# Sheet.net
KiCad netlist of a schematic drawn in Altium Designer
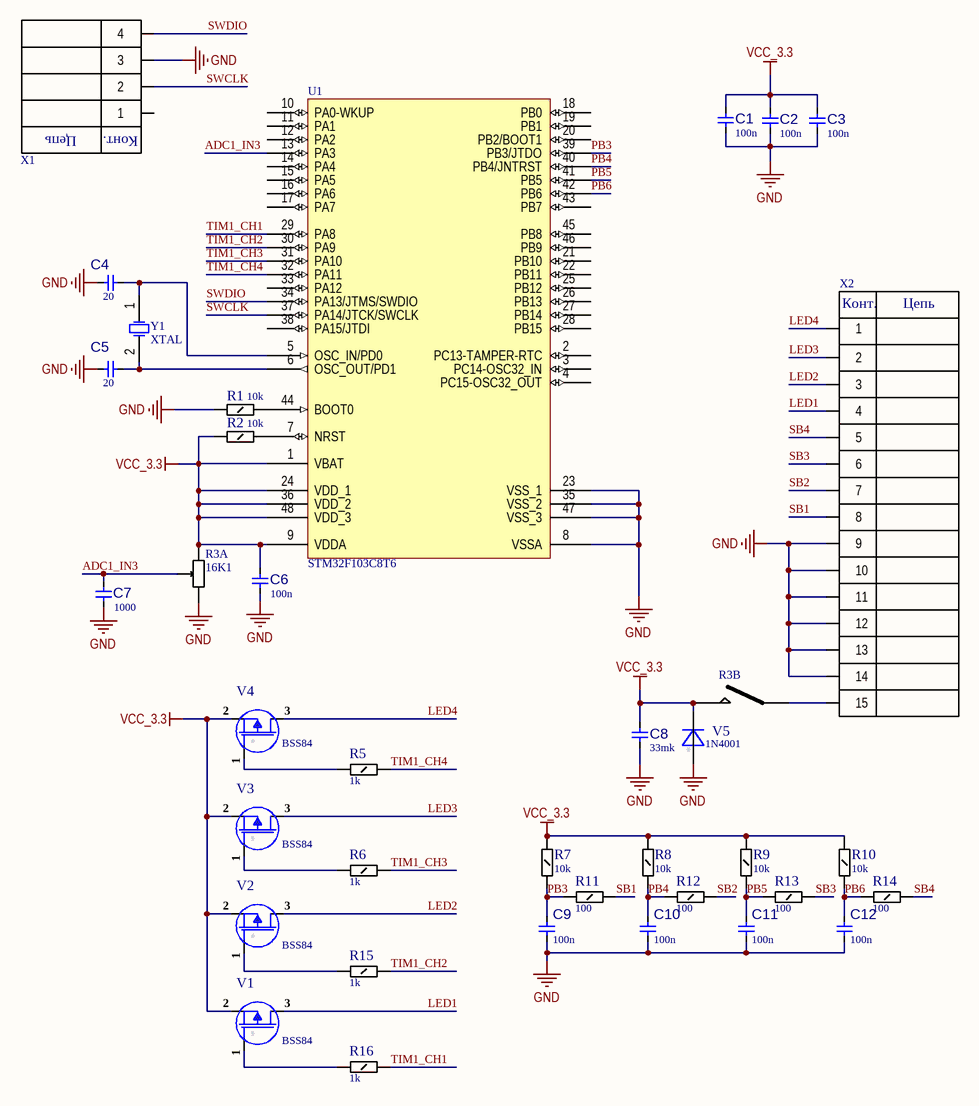
[diagram p0: Sheet.SchDoc]

(export (version "E")
  (design (tool "Eeschema 10.0.6"))
  (components
    (comp (ref "C1")
      (value "100n")
      (footprint "C1206")
      (fields (field (name "PART NUMBER") "Condensator 1206 100") (field (name "Comment") "C1206"))
      (libsource (lib "Database_Libs") (part "C1206"))
    )
    (comp (ref "C2")
      (value "100n")
      (footprint "C1206")
      (fields (field (name "PART NUMBER") "Condensator 1206 100") (field (name "Comment") "C1206"))
      (libsource (lib "Database_Libs") (part "C1206"))
    )
    (comp (ref "C3")
      (value "100n")
      (footprint "C1206")
      (fields (field (name "PART NUMBER") "Condensator 1206 100") (field (name "Comment") "C1206"))
      (libsource (lib "Database_Libs") (part "C1206"))
    )
    (comp (ref "C4")
      (value "20")
      (footprint "C1206")
      (fields (field (name "PART NUMBER") "Condensator 1206 20") (field (name "Comment") "C1206"))
      (libsource (lib "Database_Libs") (part "C1206"))
    )
    (comp (ref "C5")
      (value "20")
      (footprint "C1206")
      (fields (field (name "PART NUMBER") "Condensator 1206 20") (field (name "Comment") "C1206"))
      (libsource (lib "Database_Libs") (part "C1206"))
    )
    (comp (ref "C6")
      (value "100n")
      (footprint "C1206")
      (fields (field (name "PART NUMBER") "Condensator 1206 100") (field (name "Comment") "C1206"))
      (libsource (lib "Database_Libs") (part "C1206"))
    )
    (comp (ref "C7")
      (value "1000")
      (footprint "C1206")
      (fields (field (name "PART NUMBER") "Condensator 1206 100") (field (name "Comment") "C1206"))
      (libsource (lib "Database_Libs") (part "C1206"))
    )
    (comp (ref "C8")
      (value "33mk")
      (footprint "C1210")
      (fields (field (name "PART NUMBER") "Condensator 1210 33mk"))
      (libsource (lib "Database_Libs") (part "C1210"))
    )
    (comp (ref "C9")
      (value "100n")
      (footprint "C1206")
      (fields (field (name "PART NUMBER") "Condensator 1206 100") (field (name "Comment") "C1206"))
      (libsource (lib "Database_Libs") (part "C1206"))
    )
    (comp (ref "C10")
      (value "100n")
      (footprint "C1206")
      (fields (field (name "PART NUMBER") "Condensator 1206 100") (field (name "Comment") "C1206"))
      (libsource (lib "Database_Libs") (part "C1206"))
    )
    (comp (ref "C11")
      (value "100n")
      (footprint "C1206")
      (fields (field (name "PART NUMBER") "Condensator 1206 100") (field (name "Comment") "C1206"))
      (libsource (lib "Database_Libs") (part "C1206"))
    )
    (comp (ref "C12")
      (value "100n")
      (footprint "C1206")
      (fields (field (name "PART NUMBER") "Condensator 1206 100") (field (name "Comment") "C1206"))
      (libsource (lib "Database_Libs") (part "C1206"))
    )
    (comp (ref "R1")
      (value "10k")
      (footprint "R1206")
      (fields (field (name "PART NUMBER") "Resistor 1206 10k") (field (name "Comment") "R1206-0,25 W"))
      (libsource (lib "Database_Libs") (part "R1206-0,25 W"))
    )
    (comp (ref "R2")
      (value "10k")
      (footprint "R1206")
      (fields (field (name "PART NUMBER") "Resistor 1206 10k") (field (name "Comment") "R1206-0,25 W"))
      (libsource (lib "Database_Libs") (part "R1206-0,25 W"))
    )
    (comp (ref "R3")
      (value "16K1")
      (footprint "S16KN1")
      (fields (field (name "PART NUMBER") "Resistor S16KN1"))
      (libsource (lib "Database_Libs") (part "16K1"))
    )
    (comp (ref "R5")
      (value "1k")
      (footprint "R1206")
      (fields (field (name "PART NUMBER") "Resistor 1206 10k") (field (name "Comment") "R1206-0,25 W"))
      (libsource (lib "Database_Libs") (part "R1206-0,25 W"))
    )
    (comp (ref "R6")
      (value "1k")
      (footprint "R1206")
      (fields (field (name "PART NUMBER") "Resistor 1206 10k") (field (name "Comment") "R1206-0,25 W"))
      (libsource (lib "Database_Libs") (part "R1206-0,25 W"))
    )
    (comp (ref "R7")
      (value "10k")
      (footprint "R1206")
      (fields (field (name "PART NUMBER") "Resistor 1206 10k") (field (name "Comment") "R1206-0,25 W"))
      (libsource (lib "Database_Libs") (part "R1206-0,25 W"))
    )
    (comp (ref "R8")
      (value "10k")
      (footprint "R1206")
      (fields (field (name "PART NUMBER") "Resistor 1206 10k") (field (name "Comment") "R1206-0,25 W"))
      (libsource (lib "Database_Libs") (part "R1206-0,25 W"))
    )
    (comp (ref "R9")
      (value "10k")
      (footprint "R1206")
      (fields (field (name "PART NUMBER") "Resistor 1206 10k") (field (name "Comment") "R1206-0,25 W"))
      (libsource (lib "Database_Libs") (part "R1206-0,25 W"))
    )
    (comp (ref "R10")
      (value "10k")
      (footprint "R1206")
      (fields (field (name "PART NUMBER") "Resistor 1206 10k") (field (name "Comment") "R1206-0,25 W"))
      (libsource (lib "Database_Libs") (part "R1206-0,25 W"))
    )
    (comp (ref "R11")
      (value "100")
      (footprint "R1206")
      (fields (field (name "PART NUMBER") "Resistor 1206 10k") (field (name "Comment") "R1206-0,25 W"))
      (libsource (lib "Database_Libs") (part "R1206-0,25 W"))
    )
    (comp (ref "R12")
      (value "100")
      (footprint "R1206")
      (fields (field (name "PART NUMBER") "Resistor 1206 10k") (field (name "Comment") "R1206-0,25 W"))
      (libsource (lib "Database_Libs") (part "R1206-0,25 W"))
    )
    (comp (ref "R13")
      (value "100")
      (footprint "R1206")
      (fields (field (name "PART NUMBER") "Resistor 1206 10k") (field (name "Comment") "R1206-0,25 W"))
      (libsource (lib "Database_Libs") (part "R1206-0,25 W"))
    )
    (comp (ref "R14")
      (value "100")
      (footprint "R1206")
      (fields (field (name "PART NUMBER") "Resistor 1206 10k") (field (name "Comment") "R1206-0,25 W"))
      (libsource (lib "Database_Libs") (part "R1206-0,25 W"))
    )
    (comp (ref "R15")
      (value "1k")
      (footprint "R1206")
      (fields (field (name "PART NUMBER") "Resistor 1206 10k") (field (name "Comment") "R1206-0,25 W"))
      (libsource (lib "Database_Libs") (part "R1206-0,25 W"))
    )
    (comp (ref "R16")
      (value "1k")
      (footprint "R1206")
      (fields (field (name "PART NUMBER") "Resistor 1206 10k") (field (name "Comment") "R1206-0,25 W"))
      (libsource (lib "Database_Libs") (part "R1206-0,25 W"))
    )
    (comp (ref "U1")
      (value "STM32F103C8T6")
      (footprint "LQFP48_N")
      (description "STM32 ARM-based 32-bit MCU with 64 Kbytes Flash, 48-pin LQFP, Industrial Temperature")
      (fields (field (name "PUBLISHER") "Altium Limited"))
      (libsource (lib "ST Microcontroller 32-Bit STM32") (part "STM32F103C8T6"))
    )
    (comp (ref "V1") (value "BSS84") (footprint "SOT-23") (libsource (lib "Database_Libs") (part "BSS84")))
    (comp (ref "V2") (value "BSS84") (footprint "SOT-23") (libsource (lib "Database_Libs") (part "BSS84")))
    (comp (ref "V3") (value "BSS84") (footprint "SOT-23") (libsource (lib "Database_Libs") (part "BSS84")))
    (comp (ref "V4") (value "BSS84") (footprint "SOT-23") (libsource (lib "Database_Libs") (part "BSS84")))
    (comp (ref "V5")
      (value "1N4001")
      (footprint "doid")
      (fields (field (name "PART NUMBER") "1N4007"))
      (libsource (lib "Database_Libs") (part "1N4001"))
    )
    (comp (ref "X1")
      (value "PLS-4R")
      (footprint "PLS-4R")
      (fields (field (name "PART NUMBER") "Разъем PLS-4R"))
      (libsource (lib "Database_Libs") (part "PLS-4R"))
    )
    (comp (ref "X2")
      (value "sourse")
      (footprint "DHR15-FB")
      (fields (field (name "PART NUMBER") "DHR-15FB"))
      (libsource (lib "Database_Libs") (part "DHR"))
    )
    (comp (ref "Y1")
      (value "XTAL")
      (footprint "Crystal Oscillator:HC49/4H_SMX")
      (description "Crystal Oscillator")
      (fields (field (name "PUBLISHER") "Altium Limited"))
      (libsource (lib "Miscellaneous Devices") (part "XTAL"))
    )
  )
  (nets
    (net (code "1") (name "/ADC1_IN3") (class "Default")
      (node (ref "C7") (pin "2") (pinfunction "2_2") (pintype "passive"))
      (node (ref "R3") (pin "2") (pinfunction "2_2") (pintype "passive"))
      (node (ref "U1") (pin "13") (pinfunction "PA3_13") (pintype "bidirectional"))
    )
    (net (code "2") (name "/LED1") (class "Default")
      (node (ref "V1") (pin "3") (pinfunction "D_3") (pintype "passive"))
      (node (ref "X2") (pin "4") (pinfunction "4_4") (pintype "passive"))
    )
    (net (code "3") (name "/LED2") (class "Default")
      (node (ref "V2") (pin "3") (pinfunction "D_3") (pintype "passive"))
      (node (ref "X2") (pin "3") (pinfunction "3_3") (pintype "passive"))
    )
    (net (code "4") (name "/LED3") (class "Default")
      (node (ref "V3") (pin "3") (pinfunction "D_3") (pintype "passive"))
      (node (ref "X2") (pin "2") (pinfunction "2_2") (pintype "passive"))
    )
    (net (code "5") (name "/LED4") (class "Default")
      (node (ref "V4") (pin "3") (pinfunction "D_3") (pintype "passive"))
      (node (ref "X2") (pin "1") (pinfunction "1_1") (pintype "passive"))
    )
    (net (code "6") (name "/PB3") (class "Default")
      (node (ref "C9") (pin "2") (pinfunction "2_2") (pintype "passive"))
      (node (ref "R11") (pin "2") (pinfunction "2_2") (pintype "passive"))
      (node (ref "R7") (pin "1") (pinfunction "1_1") (pintype "passive"))
      (node (ref "U1") (pin "39") (pinfunction "PB3/JTDO_39") (pintype "bidirectional"))
    )
    (net (code "7") (name "/PB4") (class "Default")
      (node (ref "C10") (pin "2") (pinfunction "2_2") (pintype "passive"))
      (node (ref "R12") (pin "2") (pinfunction "2_2") (pintype "passive"))
      (node (ref "R8") (pin "1") (pinfunction "1_1") (pintype "passive"))
      (node (ref "U1") (pin "40") (pinfunction "PB4/JNTRST_40") (pintype "bidirectional"))
    )
    (net (code "8") (name "/PB5") (class "Default")
      (node (ref "C11") (pin "2") (pinfunction "2_2") (pintype "passive"))
      (node (ref "R13") (pin "2") (pinfunction "2_2") (pintype "passive"))
      (node (ref "R9") (pin "1") (pinfunction "1_1") (pintype "passive"))
      (node (ref "U1") (pin "41") (pinfunction "PB5_41") (pintype "bidirectional"))
    )
    (net (code "9") (name "/PB6") (class "Default")
      (node (ref "C12") (pin "2") (pinfunction "2_2") (pintype "passive"))
      (node (ref "R10") (pin "1") (pinfunction "1_1") (pintype "passive"))
      (node (ref "R14") (pin "2") (pinfunction "2_2") (pintype "passive"))
      (node (ref "U1") (pin "42") (pinfunction "PB6_42") (pintype "bidirectional"))
    )
    (net (code "10") (name "/SB1") (class "Default")
      (node (ref "R11") (pin "1") (pinfunction "1_1") (pintype "passive"))
      (node (ref "X2") (pin "8") (pinfunction "8_8") (pintype "passive"))
    )
    (net (code "11") (name "/SB2") (class "Default")
      (node (ref "R12") (pin "1") (pinfunction "1_1") (pintype "passive"))
      (node (ref "X2") (pin "7") (pinfunction "7_7") (pintype "passive"))
    )
    (net (code "12") (name "/SB3") (class "Default")
      (node (ref "R13") (pin "1") (pinfunction "1_1") (pintype "passive"))
      (node (ref "X2") (pin "6") (pinfunction "6_6") (pintype "passive"))
    )
    (net (code "13") (name "/SB4") (class "Default")
      (node (ref "R14") (pin "1") (pinfunction "1_1") (pintype "passive"))
      (node (ref "X2") (pin "5") (pinfunction "5_5") (pintype "passive"))
    )
    (net (code "14") (name "/SWCLK") (class "Default")
      (node (ref "U1") (pin "37") (pinfunction "PA14/JTCK/SWCLK_37") (pintype "bidirectional"))
      (node (ref "X1") (pin "2") (pinfunction "2_2") (pintype "passive"))
    )
    (net (code "15") (name "/SWDIO") (class "Default")
      (node (ref "U1") (pin "34") (pinfunction "PA13/JTMS/SWDIO_34") (pintype "bidirectional"))
      (node (ref "X1") (pin "4") (pinfunction "4_4") (pintype "passive"))
    )
    (net (code "16") (name "/TIM1_CH1") (class "Default")
      (node (ref "R16") (pin "1") (pinfunction "1_1") (pintype "passive"))
      (node (ref "U1") (pin "29") (pinfunction "PA8_29") (pintype "bidirectional"))
    )
    (net (code "17") (name "/TIM1_CH2") (class "Default")
      (node (ref "R15") (pin "1") (pinfunction "1_1") (pintype "passive"))
      (node (ref "U1") (pin "30") (pinfunction "PA9_30") (pintype "bidirectional"))
    )
    (net (code "18") (name "/TIM1_CH3") (class "Default")
      (node (ref "R6") (pin "1") (pinfunction "1_1") (pintype "passive"))
      (node (ref "U1") (pin "31") (pinfunction "PA10_31") (pintype "bidirectional"))
    )
    (net (code "19") (name "/TIM1_CH4") (class "Default")
      (node (ref "R5") (pin "1") (pinfunction "1_1") (pintype "passive"))
      (node (ref "U1") (pin "32") (pinfunction "PA11_32") (pintype "bidirectional"))
    )
    (net (code "20") (name "GND") (class "Default")
      (node (ref "C1") (pin "1") (pinfunction "1_1") (pintype "passive"))
      (node (ref "C10") (pin "1") (pinfunction "1_1") (pintype "passive"))
      (node (ref "C11") (pin "1") (pinfunction "1_1") (pintype "passive"))
      (node (ref "C12") (pin "1") (pinfunction "1_1") (pintype "passive"))
      (node (ref "C2") (pin "1") (pinfunction "1_1") (pintype "passive"))
      (node (ref "C3") (pin "1") (pinfunction "1_1") (pintype "passive"))
      (node (ref "C4") (pin "1") (pinfunction "1_1") (pintype "passive"))
      (node (ref "C5") (pin "1") (pinfunction "1_1") (pintype "passive"))
      (node (ref "C6") (pin "1") (pinfunction "1_1") (pintype "passive"))
      (node (ref "C7") (pin "1") (pinfunction "1_1") (pintype "passive"))
      (node (ref "C8") (pin "1") (pinfunction "1_1") (pintype "passive"))
      (node (ref "C9") (pin "1") (pinfunction "1_1") (pintype "passive"))
      (node (ref "R1") (pin "1") (pinfunction "1_1") (pintype "passive"))
      (node (ref "R3") (pin "1") (pinfunction "1_1") (pintype "passive"))
      (node (ref "U1") (pin "23") (pinfunction "VSS_1_23") (pintype "power_in"))
      (node (ref "U1") (pin "35") (pinfunction "VSS_2_35") (pintype "power_in"))
      (node (ref "U1") (pin "47") (pinfunction "VSS_3_47") (pintype "power_in"))
      (node (ref "U1") (pin "8") (pinfunction "VSSA_8") (pintype "power_in"))
      (node (ref "V5") (pin "2") (pinfunction "A_2") (pintype "passive"))
      (node (ref "X1") (pin "3") (pinfunction "3_3") (pintype "passive"))
      (node (ref "X2") (pin "10") (pinfunction "10_10") (pintype "passive"))
      (node (ref "X2") (pin "11") (pinfunction "11_11") (pintype "passive"))
      (node (ref "X2") (pin "12") (pinfunction "12_12") (pintype "passive"))
      (node (ref "X2") (pin "13") (pinfunction "13_13") (pintype "passive"))
      (node (ref "X2") (pin "14") (pinfunction "14_14") (pintype "passive"))
      (node (ref "X2") (pin "9") (pinfunction "9_9") (pintype "passive"))
    )
    (net (code "21") (name "Net-(R3-Pad5)") (class "Default")
      (node (ref "R3") (pin "5") (pinfunction "5_5") (pintype "passive"))
      (node (ref "X2") (pin "15") (pinfunction "15_15") (pintype "passive"))
    )
    (net (code "22") (name "Net-(U1-BOOT0)") (class "Default")
      (node (ref "R1") (pin "2") (pinfunction "2_2") (pintype "passive"))
      (node (ref "U1") (pin "44") (pinfunction "BOOT0_44") (pintype "input"))
    )
    (net (code "23") (name "Net-(U1-NRST)") (class "Default")
      (node (ref "R2") (pin "2") (pinfunction "2_2") (pintype "passive"))
      (node (ref "U1") (pin "7") (pinfunction "NRST_7") (pintype "bidirectional"))
    )
    (net (code "24") (name "Net-(U1-OSC_IN{slash}PD0)") (class "Default")
      (node (ref "C4") (pin "2") (pinfunction "2_2") (pintype "passive"))
      (node (ref "U1") (pin "5") (pinfunction "OSC_IN/PD0_5") (pintype "input"))
      (node (ref "Y1") (pin "1") (pinfunction "OSC1_1") (pintype "passive"))
    )
    (net (code "25") (name "Net-(U1-OSC_OUT{slash}PD1)") (class "Default")
      (node (ref "C5") (pin "2") (pinfunction "2_2") (pintype "passive"))
      (node (ref "U1") (pin "6") (pinfunction "OSC_OUT/PD1_6") (pintype "output"))
      (node (ref "Y1") (pin "2") (pinfunction "OSC2_2") (pintype "passive"))
    )
    (net (code "26") (name "Net-(V1-G)") (class "Default")
      (node (ref "R16") (pin "2") (pinfunction "2_2") (pintype "passive"))
      (node (ref "V1") (pin "1") (pinfunction "G_1") (pintype "passive"))
    )
    (net (code "27") (name "Net-(V2-G)") (class "Default")
      (node (ref "R15") (pin "2") (pinfunction "2_2") (pintype "passive"))
      (node (ref "V2") (pin "1") (pinfunction "G_1") (pintype "passive"))
    )
    (net (code "28") (name "Net-(V3-G)") (class "Default")
      (node (ref "R6") (pin "2") (pinfunction "2_2") (pintype "passive"))
      (node (ref "V3") (pin "1") (pinfunction "G_1") (pintype "passive"))
    )
    (net (code "29") (name "Net-(V4-G)") (class "Default")
      (node (ref "R5") (pin "2") (pinfunction "2_2") (pintype "passive"))
      (node (ref "V4") (pin "1") (pinfunction "G_1") (pintype "passive"))
    )
    (net (code "30") (name "VCC_3.3") (class "Default")
      (node (ref "C1") (pin "2") (pinfunction "2_2") (pintype "passive"))
      (node (ref "C2") (pin "2") (pinfunction "2_2") (pintype "passive"))
      (node (ref "C3") (pin "2") (pinfunction "2_2") (pintype "passive"))
      (node (ref "C6") (pin "2") (pinfunction "2_2") (pintype "passive"))
      (node (ref "C8") (pin "2") (pinfunction "2_2") (pintype "passive"))
      (node (ref "R10") (pin "2") (pinfunction "2_2") (pintype "passive"))
      (node (ref "R2") (pin "1") (pinfunction "1_1") (pintype "passive"))
      (node (ref "R3") (pin "3") (pinfunction "3_3") (pintype "passive"))
      (node (ref "R3") (pin "4") (pinfunction "4_4") (pintype "passive"))
      (node (ref "R7") (pin "2") (pinfunction "2_2") (pintype "passive"))
      (node (ref "R8") (pin "2") (pinfunction "2_2") (pintype "passive"))
      (node (ref "R9") (pin "2") (pinfunction "2_2") (pintype "passive"))
      (node (ref "U1") (pin "1") (pinfunction "VBAT_1") (pintype "power_in"))
      (node (ref "U1") (pin "24") (pinfunction "VDD_1_24") (pintype "power_in"))
      (node (ref "U1") (pin "36") (pinfunction "VDD_2_36") (pintype "power_in"))
      (node (ref "U1") (pin "48") (pinfunction "VDD_3_48") (pintype "power_in"))
      (node (ref "U1") (pin "9") (pinfunction "VDDA_9") (pintype "power_in"))
      (node (ref "V1") (pin "2") (pinfunction "S_2") (pintype "passive"))
      (node (ref "V2") (pin "2") (pinfunction "S_2") (pintype "passive"))
      (node (ref "V3") (pin "2") (pinfunction "S_2") (pintype "passive"))
      (node (ref "V4") (pin "2") (pinfunction "S_2") (pintype "passive"))
      (node (ref "V5") (pin "1") (pinfunction "K_1") (pintype "passive"))
    )
    (net (code "31") (name "unconnected-(U1-PA0-WKUP-Pad10)") (class "Default")
      (node (ref "U1") (pin "10") (pinfunction "PA0-WKUP_10") (pintype "bidirectional"))
    )
    (net (code "32") (name "unconnected-(U1-PA1-Pad11)") (class "Default")
      (node (ref "U1") (pin "11") (pinfunction "PA1_11") (pintype "bidirectional"))
    )
    (net (code "33") (name "unconnected-(U1-PA2-Pad12)") (class "Default")
      (node (ref "U1") (pin "12") (pinfunction "PA2_12") (pintype "bidirectional"))
    )
    (net (code "34") (name "unconnected-(U1-PA4-Pad14)") (class "Default")
      (node (ref "U1") (pin "14") (pinfunction "PA4_14") (pintype "bidirectional"))
    )
    (net (code "35") (name "unconnected-(U1-PA5-Pad15)") (class "Default")
      (node (ref "U1") (pin "15") (pinfunction "PA5_15") (pintype "bidirectional"))
    )
    (net (code "36") (name "unconnected-(U1-PA6-Pad16)") (class "Default")
      (node (ref "U1") (pin "16") (pinfunction "PA6_16") (pintype "bidirectional"))
    )
    (net (code "37") (name "unconnected-(U1-PA7-Pad17)") (class "Default")
      (node (ref "U1") (pin "17") (pinfunction "PA7_17") (pintype "bidirectional"))
    )
    (net (code "38") (name "unconnected-(U1-PA12-Pad33)") (class "Default")
      (node (ref "U1") (pin "33") (pinfunction "PA12_33") (pintype "bidirectional"))
    )
    (net (code "39") (name "unconnected-(U1-PA15{slash}JTDI-Pad38)") (class "Default")
      (node (ref "U1") (pin "38") (pinfunction "PA15/JTDI_38") (pintype "bidirectional"))
    )
    (net (code "40") (name "unconnected-(U1-PB0-Pad18)") (class "Default")
      (node (ref "U1") (pin "18") (pinfunction "PB0_18") (pintype "bidirectional"))
    )
    (net (code "41") (name "unconnected-(U1-PB1-Pad19)") (class "Default")
      (node (ref "U1") (pin "19") (pinfunction "PB1_19") (pintype "bidirectional"))
    )
    (net (code "42") (name "unconnected-(U1-PB2{slash}BOOT1-Pad20)") (class "Default")
      (node (ref "U1") (pin "20") (pinfunction "PB2/BOOT1_20") (pintype "bidirectional"))
    )
    (net (code "43") (name "unconnected-(U1-PB7-Pad43)") (class "Default")
      (node (ref "U1") (pin "43") (pinfunction "PB7_43") (pintype "bidirectional"))
    )
    (net (code "44") (name "unconnected-(U1-PB8-Pad45)") (class "Default")
      (node (ref "U1") (pin "45") (pinfunction "PB8_45") (pintype "bidirectional"))
    )
    (net (code "45") (name "unconnected-(U1-PB9-Pad46)") (class "Default")
      (node (ref "U1") (pin "46") (pinfunction "PB9_46") (pintype "bidirectional"))
    )
    (net (code "46") (name "unconnected-(U1-PB10-Pad21)") (class "Default")
      (node (ref "U1") (pin "21") (pinfunction "PB10_21") (pintype "bidirectional"))
    )
    (net (code "47") (name "unconnected-(U1-PB11-Pad22)") (class "Default")
      (node (ref "U1") (pin "22") (pinfunction "PB11_22") (pintype "bidirectional"))
    )
    (net (code "48") (name "unconnected-(U1-PB12-Pad25)") (class "Default")
      (node (ref "U1") (pin "25") (pinfunction "PB12_25") (pintype "bidirectional"))
    )
    (net (code "49") (name "unconnected-(U1-PB13-Pad26)") (class "Default")
      (node (ref "U1") (pin "26") (pinfunction "PB13_26") (pintype "bidirectional"))
    )
    (net (code "50") (name "unconnected-(U1-PB14-Pad27)") (class "Default")
      (node (ref "U1") (pin "27") (pinfunction "PB14_27") (pintype "bidirectional"))
    )
    (net (code "51") (name "unconnected-(U1-PB15-Pad28)") (class "Default")
      (node (ref "U1") (pin "28") (pinfunction "PB15_28") (pintype "bidirectional"))
    )
    (net (code "52") (name "unconnected-(U1-PC13-TAMPER-RTC-Pad2)") (class "Default")
      (node (ref "U1") (pin "2") (pinfunction "PC13-TAMPER-RTC_2") (pintype "bidirectional"))
    )
    (net (code "53") (name "unconnected-(U1-PC14-OSC32_IN-Pad3)") (class "Default")
      (node (ref "U1") (pin "3") (pinfunction "PC14-OSC32_IN_3") (pintype "bidirectional"))
    )
    (net (code "54") (name "unconnected-(U1-PC15-OSC32_OUT-Pad4)") (class "Default")
      (node (ref "U1") (pin "4") (pinfunction "PC15-OSC32_OUT_4") (pintype "bidirectional"))
    )
    (net (code "55") (name "unconnected-(X1-Pad1)") (class "Default")
      (node (ref "X1") (pin "1") (pinfunction "1_1") (pintype "passive"))
    )
  )
)
